# dBFS_Meter.net
KiCad netlist of a schematic drawn in Altium Designer
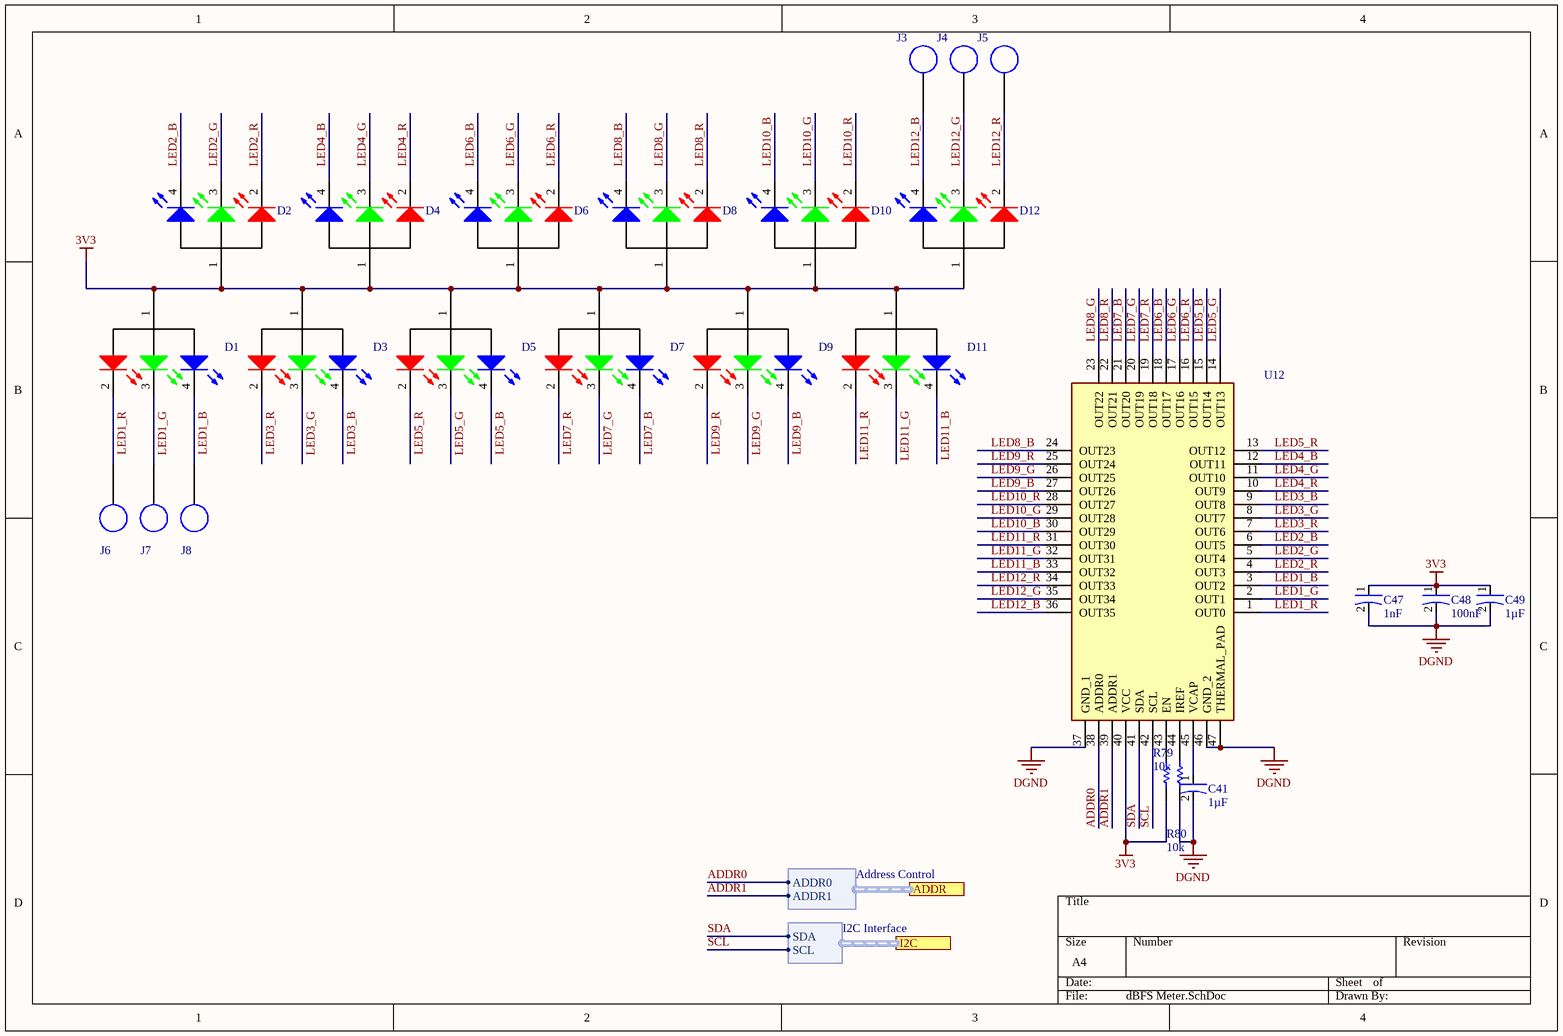
[diagram p0: dBFS Meter.SchDoc]

(export (version "E")
  (design (tool "Eeschema 10.0.6"))
  (components
    (comp (ref "C41")
      (value "1µF")
      (footprint "0805-M")
      (description "CAP 1uF CER 0805 25V C0G 10%")
      (fields (field (name "MANUFACTURER") "Generic"))
      (libsource (lib "") (part "Symbol_1"))
    )
    (comp (ref "C47")
      (value "1nF")
      (footprint "0402-M")
      (description "CAP-1nF-CER-0402-50V-X5R-10%")
      (fields (field (name "MANUFACTURER") "Generic") (field (name "Comment") "CAP 1nF CER 0402 50V X5R 10%"))
      (libsource (lib "") (part "Symbol_1"))
    )
    (comp (ref "C48")
      (value "100nF")
      (footprint "0805-M")
      (description "CAP-0.1uF-CER-0805-50V- X7R-5%")
      (fields
        (field (name "MANUFACTURER") "Generic")
        (field (name "Comment") "CAP 0.1uF CER 0805 50V  X7R 5%")
      )
      (libsource (lib "") (part "Symbol_1"))
    )
    (comp (ref "C49")
      (value "1µF")
      (footprint "0402-M")
      (description "CAP-1uF-CER-0402-25V-X5R-20%")
      (fields (field (name "MANUFACTURER") "Generic") (field (name "Comment") "CAP 1uF CER 0402 25V X5R 20%"))
      (libsource (lib "") (part "Symbol_1"))
    )
    (comp (ref "D1")
      (value "IN-B101FCH")
      (footprint "SML-LXR0804RGBC-TR")
      (description "LED-0404-RGB-10mA-3.4V")
      (fields (field (name "MANUFACTURER") "Inolux"))
      (libsource (lib "University of Malta - MEMENTO") (part "LED RGB"))
    )
    (comp (ref "D2")
      (value "IN-B101FCH")
      (footprint "SML-LXR0804RGBC-TR")
      (description "LED-0404-RGB-10mA-3.4V")
      (fields (field (name "MANUFACTURER") "Inolux"))
      (libsource (lib "University of Malta - MEMENTO") (part "LED RGB"))
    )
    (comp (ref "D3")
      (value "IN-B101FCH")
      (footprint "SML-LXR0804RGBC-TR")
      (description "LED-0404-RGB-10mA-3.4V")
      (fields (field (name "MANUFACTURER") "Inolux"))
      (libsource (lib "University of Malta - MEMENTO") (part "LED RGB"))
    )
    (comp (ref "D4")
      (value "IN-B101FCH")
      (footprint "SML-LXR0804RGBC-TR")
      (description "LED-0404-RGB-10mA-3.4V")
      (fields (field (name "MANUFACTURER") "Inolux"))
      (libsource (lib "University of Malta - MEMENTO") (part "LED RGB"))
    )
    (comp (ref "D5")
      (value "IN-B101FCH")
      (footprint "SML-LXR0804RGBC-TR")
      (description "LED-0404-RGB-10mA-3.4V")
      (fields (field (name "MANUFACTURER") "Inolux"))
      (libsource (lib "University of Malta - MEMENTO") (part "LED RGB"))
    )
    (comp (ref "D6")
      (value "IN-B101FCH")
      (footprint "SML-LXR0804RGBC-TR")
      (description "LED-0404-RGB-10mA-3.4V")
      (fields (field (name "MANUFACTURER") "Inolux"))
      (libsource (lib "University of Malta - MEMENTO") (part "LED RGB"))
    )
    (comp (ref "D7")
      (value "IN-B101FCH")
      (footprint "SML-LXR0804RGBC-TR")
      (description "LED-0404-RGB-10mA-3.4V")
      (fields (field (name "MANUFACTURER") "Inolux"))
      (libsource (lib "University of Malta - MEMENTO") (part "LED RGB"))
    )
    (comp (ref "D8")
      (value "IN-B101FCH")
      (footprint "SML-LXR0804RGBC-TR")
      (description "LED-0404-RGB-10mA-3.4V")
      (fields (field (name "MANUFACTURER") "Inolux"))
      (libsource (lib "University of Malta - MEMENTO") (part "LED RGB"))
    )
    (comp (ref "D9")
      (value "IN-B101FCH")
      (footprint "SML-LXR0804RGBC-TR")
      (description "LED-0404-RGB-10mA-3.4V")
      (fields (field (name "MANUFACTURER") "Inolux"))
      (libsource (lib "University of Malta - MEMENTO") (part "LED RGB"))
    )
    (comp (ref "D10")
      (value "IN-B101FCH")
      (footprint "SML-LXR0804RGBC-TR")
      (description "LED-0404-RGB-10mA-3.4V")
      (fields (field (name "MANUFACTURER") "Inolux"))
      (libsource (lib "University of Malta - MEMENTO") (part "LED RGB"))
    )
    (comp (ref "D11")
      (value "IN-B101FCH")
      (footprint "SML-LXR0804RGBC-TR")
      (description "LED-0404-RGB-10mA-3.4V")
      (fields (field (name "MANUFACTURER") "Inolux"))
      (libsource (lib "University of Malta - MEMENTO") (part "LED RGB"))
    )
    (comp (ref "D12")
      (value "IN-B101FCH")
      (footprint "SML-LXR0804RGBC-TR")
      (description "LED-0404-RGB-10mA-3.4V")
      (fields (field (name "MANUFACTURER") "Inolux"))
      (libsource (lib "University of Malta - MEMENTO") (part "LED RGB"))
    )
    (comp (ref "J3")
      (value "151-203-RC")
      (footprint "151-203-RC-Footprint-1")
      (description "PCB-Probe-Ring")
      (libsource (lib "University of Malta - MEMENTO") (part "PCB Probe Ring"))
    )
    (comp (ref "J4")
      (value "151-203-RC")
      (footprint "151-203-RC-Footprint-1")
      (description "PCB-Probe-Ring")
      (libsource (lib "University of Malta - MEMENTO") (part "PCB Probe Ring"))
    )
    (comp (ref "J5")
      (value "151-203-RC")
      (footprint "151-203-RC-Footprint-1")
      (description "PCB-Probe-Ring")
      (libsource (lib "University of Malta - MEMENTO") (part "PCB Probe Ring"))
    )
    (comp (ref "J6")
      (value "151-203-RC")
      (footprint "151-203-RC-Footprint-1")
      (description "PCB-Probe-Ring")
      (libsource (lib "University of Malta - MEMENTO") (part "PCB Probe Ring"))
    )
    (comp (ref "J7")
      (value "151-203-RC")
      (footprint "151-203-RC-Footprint-1")
      (description "PCB-Probe-Ring")
      (libsource (lib "University of Malta - MEMENTO") (part "PCB Probe Ring"))
    )
    (comp (ref "J8")
      (value "151-203-RC")
      (footprint "151-203-RC-Footprint-1")
      (description "PCB-Probe-Ring")
      (libsource (lib "University of Malta - MEMENTO") (part "PCB Probe Ring"))
    )
    (comp (ref "R79")
      (value "10k")
      (footprint "0402-M")
      (description "RES-10k-0402-63mW-5%")
      (fields (field (name "MANUFACTURER") "Generic") (field (name "Comment") "RES 10k 0402 63mW 5%"))
      (libsource (lib "University of Malta - MEMENTO") (part "Symbol"))
    )
    (comp (ref "R80")
      (value "10k")
      (footprint "0402-M")
      (description "RES-10k-0402-63mW-5%")
      (fields (field (name "MANUFACTURER") "Generic") (field (name "Comment") "RES 10k 0402 63mW 5%"))
      (libsource (lib "University of Malta - MEMENTO") (part "Symbol"))
    )
    (comp (ref "U12")
      (value "LP5036RJVR")
      (footprint "New footprint 1")
      (description "36-Channel LED Driver - 2.7-5.5V - 1.26A/channel")
      (fields (field (name "MANUFACTURER") "Texas Instruments"))
      (libsource (lib "University of Malta - MEMENTO") (part "LP5036RJVR"))
    )
  )
  (nets
    (net (code "5") (name "/ADDR0") (class "Default")
      (node (ref "U12") (pin "38") (pinfunction "ADDR0_38") (pintype "passive"))
    )
    (net (code "6") (name "/ADDR1") (class "Default")
      (node (ref "U12") (pin "39") (pinfunction "ADDR1_39") (pintype "passive"))
    )
    (net (code "7") (name "/LED1_B") (class "Default")
      (node (ref "D1") (pin "4") (pinfunction "B_4") (pintype "passive"))
      (node (ref "J8") (pin "1") (pinfunction "1_1") (pintype "passive"))
      (node (ref "U12") (pin "3") (pinfunction "OUT2_3") (pintype "passive"))
    )
    (net (code "8") (name "/LED1_G") (class "Default")
      (node (ref "D1") (pin "3") (pinfunction "G_3") (pintype "passive"))
      (node (ref "J7") (pin "1") (pinfunction "1_1") (pintype "passive"))
      (node (ref "U12") (pin "2") (pinfunction "OUT1_2") (pintype "passive"))
    )
    (net (code "9") (name "/LED1_R") (class "Default")
      (node (ref "D1") (pin "2") (pinfunction "R_2") (pintype "passive"))
      (node (ref "J6") (pin "1") (pinfunction "1_1") (pintype "passive"))
      (node (ref "U12") (pin "1") (pinfunction "OUT0_1") (pintype "passive"))
    )
    (net (code "10") (name "/LED2_B") (class "Default")
      (node (ref "D2") (pin "4") (pinfunction "B_4") (pintype "passive"))
      (node (ref "U12") (pin "6") (pinfunction "OUT5_6") (pintype "passive"))
    )
    (net (code "11") (name "/LED2_G") (class "Default")
      (node (ref "D2") (pin "3") (pinfunction "G_3") (pintype "passive"))
      (node (ref "U12") (pin "5") (pinfunction "OUT4_5") (pintype "passive"))
    )
    (net (code "12") (name "/LED2_R") (class "Default")
      (node (ref "D2") (pin "2") (pinfunction "R_2") (pintype "passive"))
      (node (ref "U12") (pin "4") (pinfunction "OUT3_4") (pintype "passive"))
    )
    (net (code "13") (name "/LED3_B") (class "Default")
      (node (ref "D3") (pin "4") (pinfunction "B_4") (pintype "passive"))
      (node (ref "U12") (pin "9") (pinfunction "OUT8_9") (pintype "passive"))
    )
    (net (code "14") (name "/LED3_G") (class "Default")
      (node (ref "D3") (pin "3") (pinfunction "G_3") (pintype "passive"))
      (node (ref "U12") (pin "8") (pinfunction "OUT7_8") (pintype "passive"))
    )
    (net (code "15") (name "/LED3_R") (class "Default")
      (node (ref "D3") (pin "2") (pinfunction "R_2") (pintype "passive"))
      (node (ref "U12") (pin "7") (pinfunction "OUT6_7") (pintype "passive"))
    )
    (net (code "16") (name "/LED4_B") (class "Default")
      (node (ref "D4") (pin "4") (pinfunction "B_4") (pintype "passive"))
      (node (ref "U12") (pin "12") (pinfunction "OUT11_12") (pintype "passive"))
    )
    (net (code "17") (name "/LED4_G") (class "Default")
      (node (ref "D4") (pin "3") (pinfunction "G_3") (pintype "passive"))
      (node (ref "U12") (pin "11") (pinfunction "OUT10_11") (pintype "passive"))
    )
    (net (code "18") (name "/LED4_R") (class "Default")
      (node (ref "D4") (pin "2") (pinfunction "R_2") (pintype "passive"))
      (node (ref "U12") (pin "10") (pinfunction "OUT9_10") (pintype "passive"))
    )
    (net (code "19") (name "/LED5_B") (class "Default")
      (node (ref "D5") (pin "4") (pinfunction "B_4") (pintype "passive"))
      (node (ref "U12") (pin "15") (pinfunction "OUT14_15") (pintype "passive"))
    )
    (net (code "20") (name "/LED5_G") (class "Default")
      (node (ref "D5") (pin "3") (pinfunction "G_3") (pintype "passive"))
      (node (ref "U12") (pin "14") (pinfunction "OUT13_14") (pintype "passive"))
    )
    (net (code "21") (name "/LED5_R") (class "Default")
      (node (ref "D5") (pin "2") (pinfunction "R_2") (pintype "passive"))
      (node (ref "U12") (pin "13") (pinfunction "OUT12_13") (pintype "passive"))
    )
    (net (code "22") (name "/LED6_B") (class "Default")
      (node (ref "D6") (pin "4") (pinfunction "B_4") (pintype "passive"))
      (node (ref "U12") (pin "18") (pinfunction "OUT17_18") (pintype "passive"))
    )
    (net (code "23") (name "/LED6_G") (class "Default")
      (node (ref "D6") (pin "3") (pinfunction "G_3") (pintype "passive"))
      (node (ref "U12") (pin "17") (pinfunction "OUT16_17") (pintype "passive"))
    )
    (net (code "24") (name "/LED6_R") (class "Default")
      (node (ref "D6") (pin "2") (pinfunction "R_2") (pintype "passive"))
      (node (ref "U12") (pin "16") (pinfunction "OUT15_16") (pintype "passive"))
    )
    (net (code "25") (name "/LED7_B") (class "Default")
      (node (ref "D7") (pin "4") (pinfunction "B_4") (pintype "passive"))
      (node (ref "U12") (pin "21") (pinfunction "OUT20_21") (pintype "passive"))
    )
    (net (code "26") (name "/LED7_G") (class "Default")
      (node (ref "D7") (pin "3") (pinfunction "G_3") (pintype "passive"))
      (node (ref "U12") (pin "20") (pinfunction "OUT19_20") (pintype "passive"))
    )
    (net (code "27") (name "/LED7_R") (class "Default")
      (node (ref "D7") (pin "2") (pinfunction "R_2") (pintype "passive"))
      (node (ref "U12") (pin "19") (pinfunction "OUT18_19") (pintype "passive"))
    )
    (net (code "28") (name "/LED8_B") (class "Default")
      (node (ref "D8") (pin "4") (pinfunction "B_4") (pintype "passive"))
      (node (ref "U12") (pin "24") (pinfunction "OUT23_24") (pintype "passive"))
    )
    (net (code "29") (name "/LED8_G") (class "Default")
      (node (ref "D8") (pin "3") (pinfunction "G_3") (pintype "passive"))
      (node (ref "U12") (pin "23") (pinfunction "OUT22_23") (pintype "passive"))
    )
    (net (code "30") (name "/LED8_R") (class "Default")
      (node (ref "D8") (pin "2") (pinfunction "R_2") (pintype "passive"))
      (node (ref "U12") (pin "22") (pinfunction "OUT21_22") (pintype "passive"))
    )
    (net (code "31") (name "/LED9_B") (class "Default")
      (node (ref "D9") (pin "4") (pinfunction "B_4") (pintype "passive"))
      (node (ref "U12") (pin "27") (pinfunction "OUT26_27") (pintype "passive"))
    )
    (net (code "32") (name "/LED9_G") (class "Default")
      (node (ref "D9") (pin "3") (pinfunction "G_3") (pintype "passive"))
      (node (ref "U12") (pin "26") (pinfunction "OUT25_26") (pintype "passive"))
    )
    (net (code "33") (name "/LED9_R") (class "Default")
      (node (ref "D9") (pin "2") (pinfunction "R_2") (pintype "passive"))
      (node (ref "U12") (pin "25") (pinfunction "OUT24_25") (pintype "passive"))
    )
    (net (code "34") (name "/LED10_B") (class "Default")
      (node (ref "D10") (pin "4") (pinfunction "B_4") (pintype "passive"))
      (node (ref "U12") (pin "30") (pinfunction "OUT29_30") (pintype "passive"))
    )
    (net (code "35") (name "/LED10_G") (class "Default")
      (node (ref "D10") (pin "3") (pinfunction "G_3") (pintype "passive"))
      (node (ref "U12") (pin "29") (pinfunction "OUT28_29") (pintype "passive"))
    )
    (net (code "36") (name "/LED10_R") (class "Default")
      (node (ref "D10") (pin "2") (pinfunction "R_2") (pintype "passive"))
      (node (ref "U12") (pin "28") (pinfunction "OUT27_28") (pintype "passive"))
    )
    (net (code "37") (name "/LED11_B") (class "Default")
      (node (ref "D11") (pin "4") (pinfunction "B_4") (pintype "passive"))
      (node (ref "U12") (pin "33") (pinfunction "OUT32_33") (pintype "passive"))
    )
    (net (code "38") (name "/LED11_G") (class "Default")
      (node (ref "D11") (pin "3") (pinfunction "G_3") (pintype "passive"))
      (node (ref "U12") (pin "32") (pinfunction "OUT31_32") (pintype "passive"))
    )
    (net (code "39") (name "/LED11_R") (class "Default")
      (node (ref "D11") (pin "2") (pinfunction "R_2") (pintype "passive"))
      (node (ref "U12") (pin "31") (pinfunction "OUT30_31") (pintype "passive"))
    )
    (net (code "40") (name "/LED12_B") (class "Default")
      (node (ref "D12") (pin "4") (pinfunction "B_4") (pintype "passive"))
      (node (ref "J3") (pin "1") (pinfunction "1_1") (pintype "passive"))
      (node (ref "U12") (pin "36") (pinfunction "OUT35_36") (pintype "passive"))
    )
    (net (code "41") (name "/LED12_G") (class "Default")
      (node (ref "D12") (pin "3") (pinfunction "G_3") (pintype "passive"))
      (node (ref "J4") (pin "1") (pinfunction "1_1") (pintype "passive"))
      (node (ref "U12") (pin "35") (pinfunction "OUT34_35") (pintype "passive"))
    )
    (net (code "42") (name "/LED12_R") (class "Default")
      (node (ref "D12") (pin "2") (pinfunction "R_2") (pintype "passive"))
      (node (ref "J5") (pin "1") (pinfunction "1_1") (pintype "passive"))
      (node (ref "U12") (pin "34") (pinfunction "OUT33_34") (pintype "passive"))
    )
    (net (code "43") (name "/SCL") (class "Default")
      (node (ref "U12") (pin "42") (pinfunction "SCL_42") (pintype "passive"))
    )
    (net (code "44") (name "/SDA") (class "Default")
      (node (ref "U12") (pin "41") (pinfunction "SDA_41") (pintype "passive"))
    )
    (net (code "47") (name "3V3") (class "Default")
      (node (ref "C47") (pin "1") (pinfunction "Anode_1") (pintype "passive"))
      (node (ref "C48") (pin "1") (pinfunction "Anode_1") (pintype "passive"))
      (node (ref "C49") (pin "1") (pinfunction "Anode_1") (pintype "passive"))
      (node (ref "D1") (pin "1") (pinfunction "A_1") (pintype "passive"))
      (node (ref "D10") (pin "1") (pinfunction "A_1") (pintype "passive"))
      (node (ref "D11") (pin "1") (pinfunction "A_1") (pintype "passive"))
      (node (ref "D12") (pin "1") (pinfunction "A_1") (pintype "passive"))
      (node (ref "D2") (pin "1") (pinfunction "A_1") (pintype "passive"))
      (node (ref "D3") (pin "1") (pinfunction "A_1") (pintype "passive"))
      (node (ref "D4") (pin "1") (pinfunction "A_1") (pintype "passive"))
      (node (ref "D5") (pin "1") (pinfunction "A_1") (pintype "passive"))
      (node (ref "D6") (pin "1") (pinfunction "A_1") (pintype "passive"))
      (node (ref "D7") (pin "1") (pinfunction "A_1") (pintype "passive"))
      (node (ref "D8") (pin "1") (pinfunction "A_1") (pintype "passive"))
      (node (ref "D9") (pin "1") (pinfunction "A_1") (pintype "passive"))
      (node (ref "R79") (pin "1") (pinfunction "1_1") (pintype "passive"))
      (node (ref "U12") (pin "40") (pinfunction "VCC_40") (pintype "passive"))
    )
    (net (code "48") (name "DGND") (class "Default")
      (node (ref "C41") (pin "2") (pinfunction "Cathode_2") (pintype "passive"))
      (node (ref "C47") (pin "2") (pinfunction "Cathode_2") (pintype "passive"))
      (node (ref "C48") (pin "2") (pinfunction "Cathode_2") (pintype "passive"))
      (node (ref "C49") (pin "2") (pinfunction "Cathode_2") (pintype "passive"))
      (node (ref "R80") (pin "1") (pinfunction "1_1") (pintype "passive"))
      (node (ref "U12") (pin "37") (pinfunction "GND_1_37") (pintype "passive"))
      (node (ref "U12") (pin "46") (pinfunction "GND_2_46") (pintype "passive"))
      (node (ref "U12") (pin "47") (pinfunction "THERMAL_PAD_47") (pintype "power_in"))
    )
    (net (code "49") (name "Net-(C41-Anode)") (class "Default")
      (node (ref "C41") (pin "1") (pinfunction "Anode_1") (pintype "passive"))
      (node (ref "U12") (pin "45") (pinfunction "VCAP_45") (pintype "passive"))
    )
    (net (code "50") (name "Net-(U12-EN)") (class "Default")
      (node (ref "R79") (pin "2") (pinfunction "2_2") (pintype "passive"))
      (node (ref "U12") (pin "43") (pinfunction "EN_43") (pintype "passive"))
    )
    (net (code "51") (name "Net-(U12-IREF)") (class "Default")
      (node (ref "R80") (pin "2") (pinfunction "2_2") (pintype "passive"))
      (node (ref "U12") (pin "44") (pinfunction "IREF_44") (pintype "passive"))
    )
  )
)
